# sch.net
KiCad netlist of a schematic drawn in Altium Designer
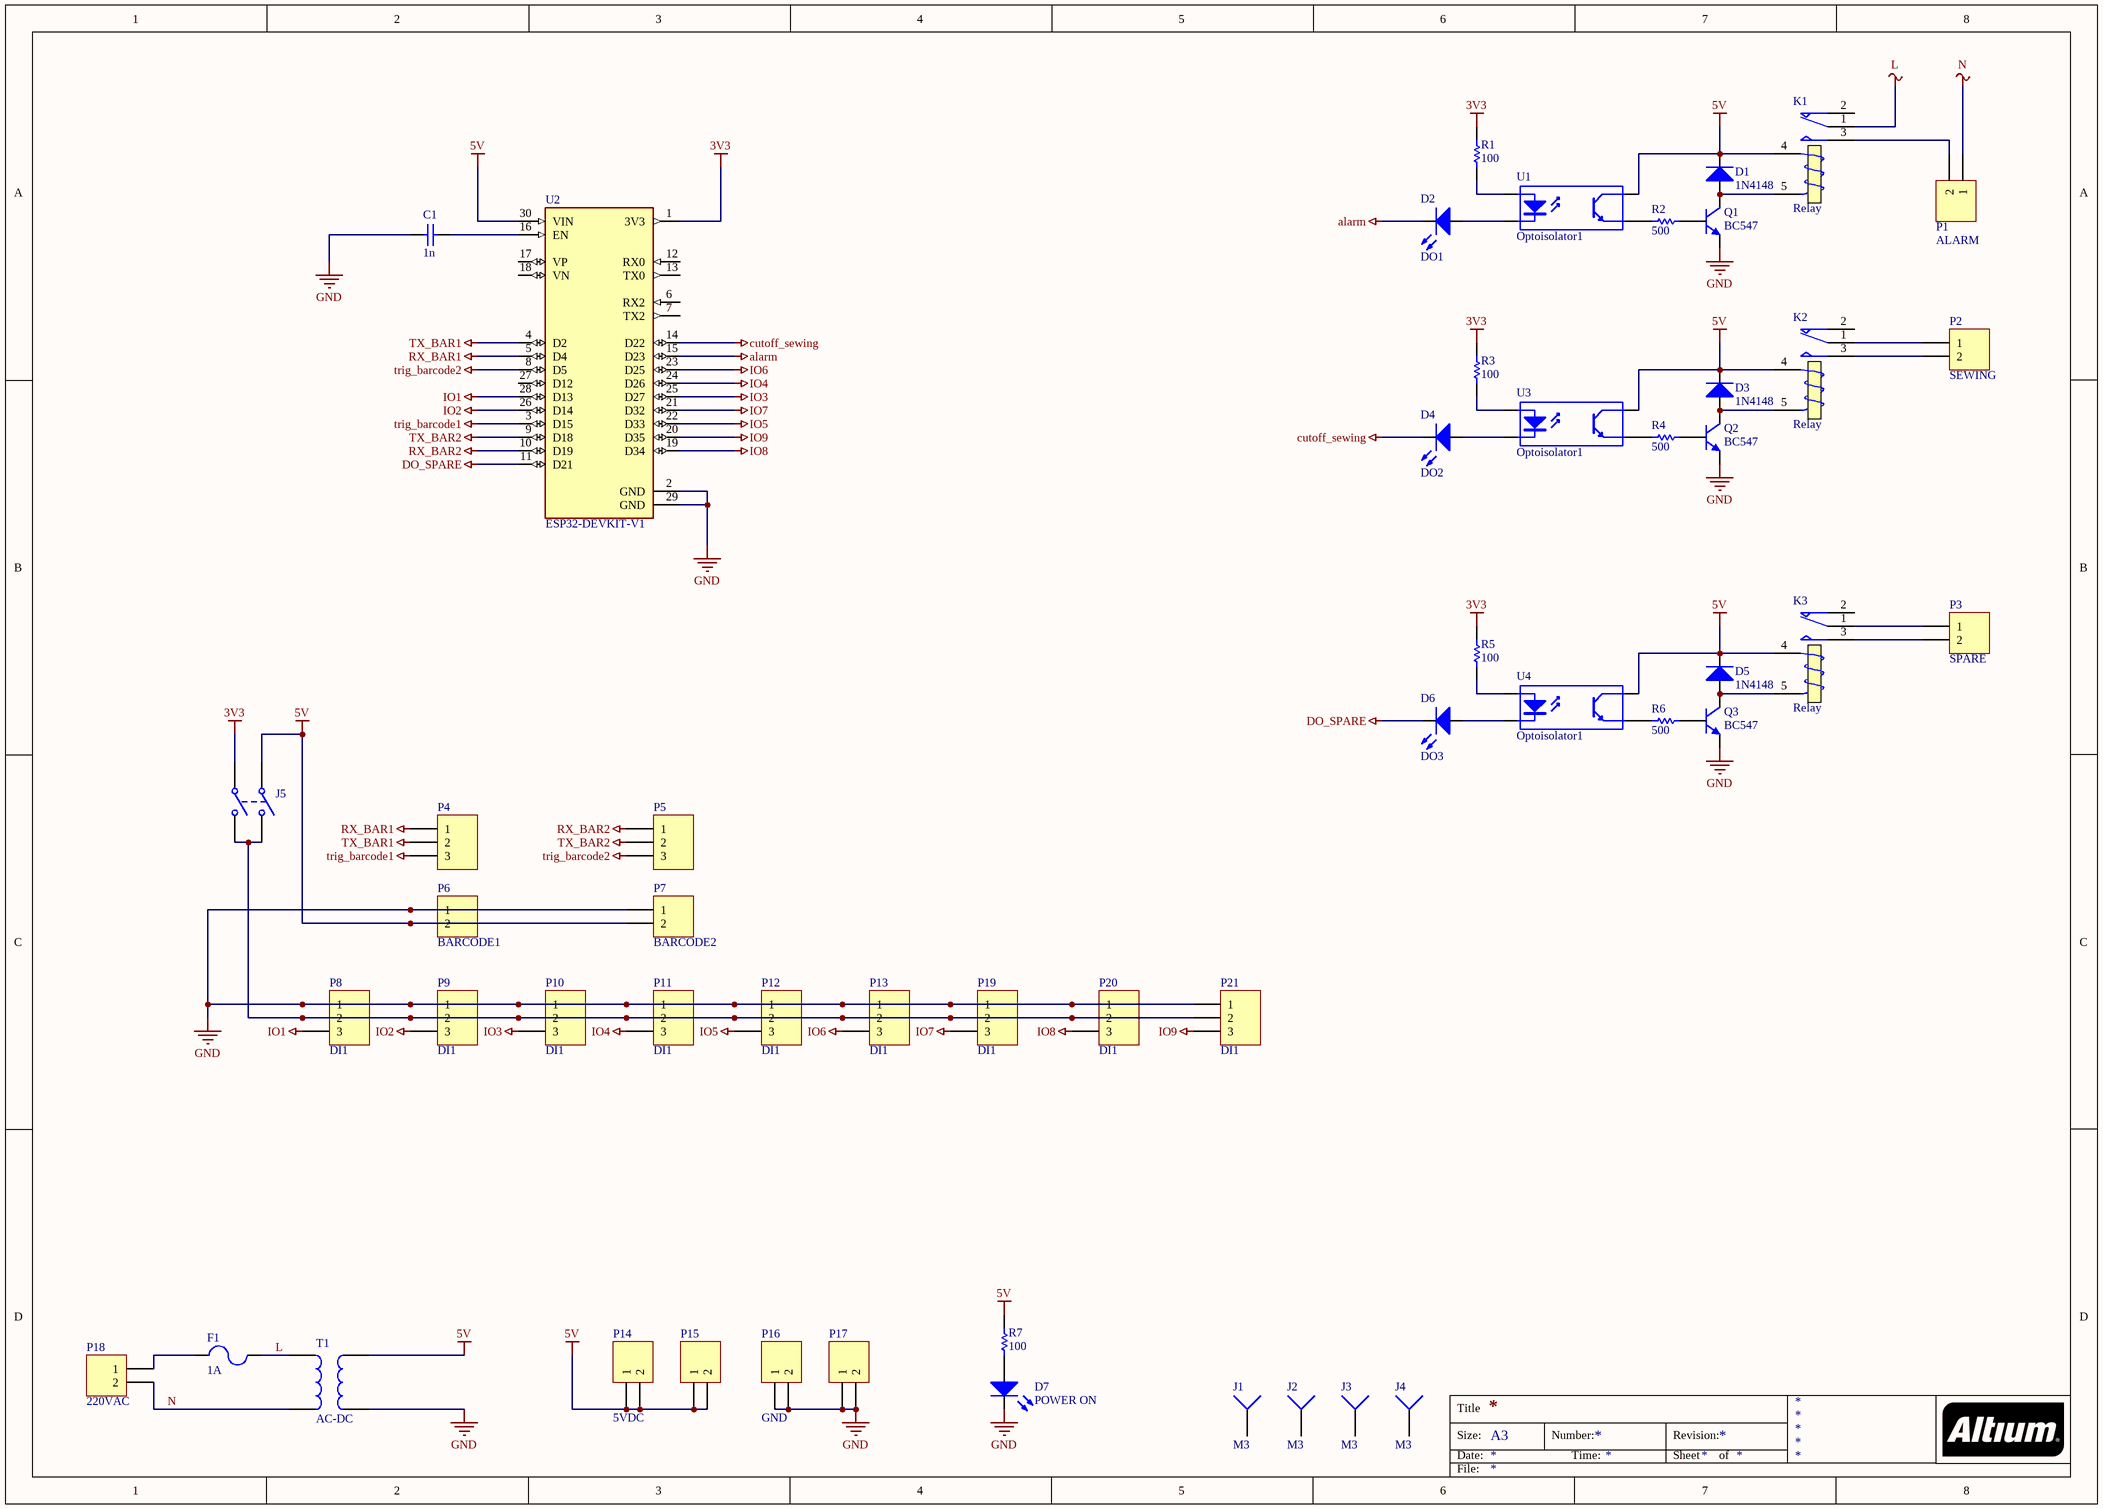
[diagram p0: sch.SchDoc]

(export (version "E")
  (design (tool "Eeschema 10.0.6"))
  (components
    (comp (ref "C1")
      (value "1n")
      (footprint "weerachai:CR2012-0805")
      (description "Capacitor")
      (fields (field (name "PUBLISHER") "Altium Limited"))
      (libsource (lib "Miscellaneous Devices") (part "Cap"))
    )
    (comp (ref "D1")
      (value "1N4148")
      (footprint "weerachai:D4148")
      (description "Default Diode")
      (fields (field (name "PUBLISHER") "Altium Limited"))
      (libsource (lib "weerachai") (part "Diode"))
    )
    (comp (ref "D2")
      (value "DO1")
      (footprint "weerachai:LED")
      (description "Typical INFRARED GaAs LED")
      (fields (field (name "PUBLISHER") "Altium Limited"))
      (libsource (lib "weerachai") (part "LED0"))
    )
    (comp (ref "D3")
      (value "1N4148")
      (footprint "weerachai:D4148")
      (description "Default Diode")
      (fields (field (name "PUBLISHER") "Altium Limited"))
      (libsource (lib "weerachai") (part "Diode"))
    )
    (comp (ref "D4")
      (value "DO2")
      (footprint "weerachai:LED")
      (description "Typical INFRARED GaAs LED")
      (fields (field (name "PUBLISHER") "Altium Limited"))
      (libsource (lib "weerachai") (part "LED0"))
    )
    (comp (ref "D5")
      (value "1N4148")
      (footprint "weerachai:D4148")
      (description "Default Diode")
      (fields (field (name "PUBLISHER") "Altium Limited"))
      (libsource (lib "weerachai") (part "Diode"))
    )
    (comp (ref "D6")
      (value "DO3")
      (footprint "weerachai:LED")
      (description "Typical INFRARED GaAs LED")
      (fields (field (name "PUBLISHER") "Altium Limited"))
      (libsource (lib "weerachai") (part "LED0"))
    )
    (comp (ref "D7")
      (value "POWER ON")
      (footprint "weerachai:LED")
      (description "Typical INFRARED GaAs LED")
      (fields (field (name "PUBLISHER") "Altium Limited"))
      (libsource (lib "weerachai") (part "LED0"))
    )
    (comp (ref "F1")
      (value "1A")
      (footprint "weerachai:CAP5W")
      (description "Fuse")
      (fields (field (name "PUBLISHER") "Altium Limited"))
      (libsource (lib "weerachai") (part "Fuse 2"))
    )
    (comp (ref "J1")
      (value "M3")
      (footprint "weerachai:PAD")
      (description "Socket")
      (fields (field (name "PUBLISHER") "Altium Limited"))
      (libsource (lib "weerachai") (part "Socket"))
    )
    (comp (ref "J2")
      (value "M3")
      (footprint "weerachai:PAD")
      (description "Socket")
      (fields (field (name "PUBLISHER") "Altium Limited"))
      (libsource (lib "weerachai") (part "Socket"))
    )
    (comp (ref "J3")
      (value "M3")
      (footprint "weerachai:PAD")
      (description "Socket")
      (fields (field (name "PUBLISHER") "Altium Limited"))
      (libsource (lib "weerachai") (part "Socket"))
    )
    (comp (ref "J4")
      (value "M3")
      (footprint "weerachai:PAD")
      (description "Socket")
      (fields (field (name "PUBLISHER") "Altium Limited"))
      (libsource (lib "weerachai") (part "Socket"))
    )
    (comp (ref "J5")
      (value "~")
      (footprint "weerachai:sip2x2")
      (description "Double-Pole, Single-Throw Switch")
      (fields (field (name "PUBLISHER") "Altium Limited"))
      (libsource (lib "Miscellaneous Devices") (part "SW-DPST"))
    )
    (comp (ref "K1")
      (value "Relay")
      (footprint "weerachai:RELAY1CON_REV")
      (description "SPDT Relay")
      (fields (field (name "PUBLISHER") "Altium Limited"))
      (libsource (lib "weerachai") (part "Relay"))
    )
    (comp (ref "K2")
      (value "Relay")
      (footprint "weerachai:RELAY1CON_REV")
      (description "SPDT Relay")
      (fields (field (name "PUBLISHER") "Altium Limited"))
      (libsource (lib "weerachai") (part "Relay"))
    )
    (comp (ref "K3")
      (value "Relay")
      (footprint "weerachai:RELAY1CON_REV")
      (description "SPDT Relay")
      (fields (field (name "PUBLISHER") "Altium Limited"))
      (libsource (lib "weerachai") (part "Relay"))
    )
    (comp (ref "P1")
      (value "ALARM")
      (footprint "weerachai:KF142V-5.08-P2")
      (description "Header, 2-Pin")
      (fields (field (name "PUBLISHER") "Altium Limited"))
      (libsource (lib "") (part "Header 2_2"))
    )
    (comp (ref "P2")
      (value "SEWING")
      (footprint "weerachai:KF142V-5.08-P2")
      (description "Header, 2-Pin")
      (fields (field (name "PUBLISHER") "Altium Limited"))
      (libsource (lib "") (part "Header 2_1"))
    )
    (comp (ref "P3")
      (value "SPARE")
      (footprint "weerachai:KF142V-5.08-P2")
      (description "Header, 2-Pin")
      (fields (field (name "PUBLISHER") "Altium Limited"))
      (libsource (lib "") (part "Header 2_1"))
    )
    (comp (ref "P4")
      (value "~")
      (footprint "weerachai:CONNECT_W(3)")
      (description "Header, 3-Pin")
      (fields (field (name "PUBLISHER") "Altium Limited"))
      (libsource (lib "Miscellaneous Connectors") (part "Header 3"))
    )
    (comp (ref "P5")
      (value "~")
      (footprint "weerachai:CONNECT_W(3)")
      (description "Header, 3-Pin")
      (fields (field (name "PUBLISHER") "Altium Limited"))
      (libsource (lib "Miscellaneous Connectors") (part "Header 3"))
    )
    (comp (ref "P6")
      (value "BARCODE1")
      (footprint "weerachai:CONNECT_2.54_(2)")
      (description "Header, 2-Pin")
      (fields (field (name "PUBLISHER") "Altium Limited"))
      (libsource (lib "") (part "Header 2_1"))
    )
    (comp (ref "P7")
      (value "BARCODE2")
      (footprint "weerachai:CONNECT_2.54_(2)")
      (description "Header, 2-Pin")
      (fields (field (name "PUBLISHER") "Altium Limited"))
      (libsource (lib "") (part "Header 2_1"))
    )
    (comp (ref "P8")
      (value "DI1")
      (footprint "weerachai:CONNECT_W(3)")
      (description "Header, 3-Pin")
      (fields (field (name "PUBLISHER") "Altium Limited"))
      (libsource (lib "Miscellaneous Connectors") (part "Header 3"))
    )
    (comp (ref "P9")
      (value "DI1")
      (footprint "weerachai:CONNECT_W(3)")
      (description "Header, 3-Pin")
      (fields (field (name "PUBLISHER") "Altium Limited"))
      (libsource (lib "Miscellaneous Connectors") (part "Header 3"))
    )
    (comp (ref "P10")
      (value "DI1")
      (footprint "weerachai:CONNECT_W(3)")
      (description "Header, 3-Pin")
      (fields (field (name "PUBLISHER") "Altium Limited"))
      (libsource (lib "Miscellaneous Connectors") (part "Header 3"))
    )
    (comp (ref "P11")
      (value "DI1")
      (footprint "weerachai:CONNECT_W(3)")
      (description "Header, 3-Pin")
      (fields (field (name "PUBLISHER") "Altium Limited"))
      (libsource (lib "Miscellaneous Connectors") (part "Header 3"))
    )
    (comp (ref "P12")
      (value "DI1")
      (footprint "weerachai:CONNECT_W(3)")
      (description "Header, 3-Pin")
      (fields (field (name "PUBLISHER") "Altium Limited"))
      (libsource (lib "Miscellaneous Connectors") (part "Header 3"))
    )
    (comp (ref "P13")
      (value "DI1")
      (footprint "weerachai:CONNECT_W(3)")
      (description "Header, 3-Pin")
      (fields (field (name "PUBLISHER") "Altium Limited"))
      (libsource (lib "Miscellaneous Connectors") (part "Header 3"))
    )
    (comp (ref "P14")
      (value "5VDC")
      (footprint "weerachai:KF142V-5.08-P2")
      (description "Header, 2-Pin")
      (fields (field (name "PUBLISHER") "Altium Limited"))
      (libsource (lib "Miscellaneous Connectors") (part "Header 2"))
    )
    (comp (ref "P15")
      (value "~")
      (footprint "weerachai:KF142V-5.08-P2")
      (description "Header, 2-Pin")
      (fields (field (name "PUBLISHER") "Altium Limited"))
      (libsource (lib "Miscellaneous Connectors") (part "Header 2"))
    )
    (comp (ref "P16")
      (value "GND")
      (footprint "weerachai:KF142V-5.08-P2")
      (description "Header, 2-Pin")
      (fields (field (name "PUBLISHER") "Altium Limited"))
      (libsource (lib "Miscellaneous Connectors") (part "Header 2"))
    )
    (comp (ref "P17")
      (value "~")
      (footprint "weerachai:KF142V-5.08-P2")
      (description "Header, 2-Pin")
      (fields (field (name "PUBLISHER") "Altium Limited"))
      (libsource (lib "Miscellaneous Connectors") (part "Header 2"))
    )
    (comp (ref "P18")
      (value "220VAC")
      (footprint "weerachai:KF142V-5.08-P2")
      (description "Header, 2-Pin")
      (fields (field (name "PUBLISHER") "Altium Limited"))
      (libsource (lib "") (part "Header 2_2"))
    )
    (comp (ref "P19")
      (value "DI1")
      (footprint "weerachai:CONNECT_W(3)")
      (description "Header, 3-Pin")
      (fields (field (name "PUBLISHER") "Altium Limited"))
      (libsource (lib "Miscellaneous Connectors") (part "Header 3"))
    )
    (comp (ref "P20")
      (value "DI1")
      (footprint "weerachai:CONNECT_W(3)")
      (description "Header, 3-Pin")
      (fields (field (name "PUBLISHER") "Altium Limited"))
      (libsource (lib "Miscellaneous Connectors") (part "Header 3"))
    )
    (comp (ref "P21")
      (value "DI1")
      (footprint "weerachai:CONNECT_W(3)")
      (description "Header, 3-Pin")
      (fields (field (name "PUBLISHER") "Altium Limited"))
      (libsource (lib "Miscellaneous Connectors") (part "Header 3"))
    )
    (comp (ref "Q1")
      (value "BC547")
      (footprint "weerachai:TO-92")
      (description "NPN General Purpose Amplifier")
      (fields (field (name "PUBLISHER") "Altium Limited"))
      (libsource (lib "weerachai") (part "2N3904"))
    )
    (comp (ref "Q2")
      (value "BC547")
      (footprint "weerachai:TO-92")
      (description "NPN General Purpose Amplifier")
      (fields (field (name "PUBLISHER") "Altium Limited"))
      (libsource (lib "weerachai") (part "2N3904"))
    )
    (comp (ref "Q3")
      (value "BC547")
      (footprint "weerachai:TO-92")
      (description "NPN General Purpose Amplifier")
      (fields (field (name "PUBLISHER") "Altium Limited"))
      (libsource (lib "weerachai") (part "2N3904"))
    )
    (comp (ref "R1")
      (value "100")
      (footprint "weerachai:R1/8")
      (description "Resistor")
      (fields (field (name "PUBLISHER") "Altium Limited"))
      (libsource (lib "weerachai") (part "Res1"))
    )
    (comp (ref "R2")
      (value "500")
      (footprint "weerachai:R1/8")
      (description "Resistor")
      (fields (field (name "PUBLISHER") "Altium Limited"))
      (libsource (lib "weerachai") (part "Res1"))
    )
    (comp (ref "R3")
      (value "100")
      (footprint "weerachai:R1/8")
      (description "Resistor")
      (fields (field (name "PUBLISHER") "Altium Limited"))
      (libsource (lib "weerachai") (part "Res1"))
    )
    (comp (ref "R4")
      (value "500")
      (footprint "weerachai:R1/8")
      (description "Resistor")
      (fields (field (name "PUBLISHER") "Altium Limited"))
      (libsource (lib "weerachai") (part "Res1"))
    )
    (comp (ref "R5")
      (value "100")
      (footprint "weerachai:R1/8")
      (description "Resistor")
      (fields (field (name "PUBLISHER") "Altium Limited"))
      (libsource (lib "weerachai") (part "Res1"))
    )
    (comp (ref "R6")
      (value "500")
      (footprint "weerachai:R1/8")
      (description "Resistor")
      (fields (field (name "PUBLISHER") "Altium Limited"))
      (libsource (lib "weerachai") (part "Res1"))
    )
    (comp (ref "R7")
      (value "100")
      (footprint "weerachai:R1/8")
      (description "Resistor")
      (fields (field (name "PUBLISHER") "Altium Limited"))
      (libsource (lib "weerachai") (part "Res1"))
    )
    (comp (ref "T1")
      (value "AC-DC")
      (footprint "weerachai:HLK-PM01")
      (description "Transformer")
      (fields (field (name "PUBLISHER") "Altium Limited"))
      (libsource (lib "weerachai") (part "Trans"))
    )
    (comp (ref "U1")
      (value "Optoisolator1")
      (footprint "weerachai:DIP-4 - TOP")
      (description "4-Pin Phototransistor Optocoupler")
      (fields (field (name "PUBLISHER") "Altium Limited"))
      (libsource (lib "weerachai") (part "Optoisolator1"))
    )
    (comp (ref "U2")
      (value "ESP32-DEVKIT-V1")
      (footprint "weerachai:ESP32_DEVKIT_V1")
      (libsource (lib "weerachai") (part "ESP32-DEVKIT-V1"))
    )
    (comp (ref "U3")
      (value "Optoisolator1")
      (footprint "weerachai:DIP-4 - TOP")
      (description "4-Pin Phototransistor Optocoupler")
      (fields (field (name "PUBLISHER") "Altium Limited"))
      (libsource (lib "weerachai") (part "Optoisolator1"))
    )
    (comp (ref "U4")
      (value "Optoisolator1")
      (footprint "weerachai:DIP-4 - TOP")
      (description "4-Pin Phototransistor Optocoupler")
      (fields (field (name "PUBLISHER") "Altium Limited"))
      (libsource (lib "weerachai") (part "Optoisolator1"))
    )
  )
  (nets
    (net (code "1") (name "3V3") (class "Default")
      (node (ref "J5") (pin "3") (pinfunction "COMMON2_3") (pintype "passive"))
      (node (ref "R1") (pin "2") (pinfunction "2_2") (pintype "passive"))
      (node (ref "R3") (pin "2") (pinfunction "2_2") (pintype "passive"))
      (node (ref "R5") (pin "2") (pinfunction "2_2") (pintype "passive"))
      (node (ref "U2") (pin "1") (pinfunction "3V3_1") (pintype "output"))
    )
    (net (code "2") (name "5V") (class "Default")
      (node (ref "D1") (pin "K") (pinfunction "K_K") (pintype "passive"))
      (node (ref "D3") (pin "K") (pinfunction "K_K") (pintype "passive"))
      (node (ref "D5") (pin "K") (pinfunction "K_K") (pintype "passive"))
      (node (ref "J5") (pin "1") (pinfunction "COMMON1_1") (pintype "passive"))
      (node (ref "K1") (pin "4") (pinfunction "T1_4") (pintype "passive"))
      (node (ref "K2") (pin "4") (pinfunction "T1_4") (pintype "passive"))
      (node (ref "K3") (pin "4") (pinfunction "T1_4") (pintype "passive"))
      (node (ref "P14") (pin "1") (pinfunction "1_1") (pintype "passive"))
      (node (ref "P14") (pin "2") (pinfunction "2_2") (pintype "passive"))
      (node (ref "P15") (pin "1") (pinfunction "1_1") (pintype "passive"))
      (node (ref "P15") (pin "2") (pinfunction "2_2") (pintype "passive"))
      (node (ref "P6") (pin "2") (pinfunction "2_2") (pintype "passive"))
      (node (ref "P7") (pin "2") (pinfunction "2_2") (pintype "passive"))
      (node (ref "R7") (pin "1") (pinfunction "1_1") (pintype "passive"))
      (node (ref "T1") (pin "4") (pinfunction "4_4") (pintype "passive"))
      (node (ref "U1") (pin "4") (pinfunction "C_4") (pintype "passive"))
      (node (ref "U2") (pin "30") (pinfunction "VIN_30") (pintype "input"))
      (node (ref "U3") (pin "4") (pinfunction "C_4") (pintype "passive"))
      (node (ref "U4") (pin "4") (pinfunction "C_4") (pintype "passive"))
    )
    (net (code "3") (name "DO_SPARE") (class "Default")
      (node (ref "D6") (pin "2") (pinfunction "K_2") (pintype "passive"))
      (node (ref "U2") (pin "11") (pinfunction "D21_11") (pintype "bidirectional"))
    )
    (net (code "4") (name "GND") (class "Default")
      (node (ref "C1") (pin "1") (pinfunction "1_1") (pintype "passive"))
      (node (ref "D7") (pin "2") (pinfunction "K_2") (pintype "passive"))
      (node (ref "P10") (pin "1") (pinfunction "1_1") (pintype "passive"))
      (node (ref "P11") (pin "1") (pinfunction "1_1") (pintype "passive"))
      (node (ref "P12") (pin "1") (pinfunction "1_1") (pintype "passive"))
      (node (ref "P13") (pin "1") (pinfunction "1_1") (pintype "passive"))
      (node (ref "P16") (pin "1") (pinfunction "1_1") (pintype "passive"))
      (node (ref "P16") (pin "2") (pinfunction "2_2") (pintype "passive"))
      (node (ref "P17") (pin "1") (pinfunction "1_1") (pintype "passive"))
      (node (ref "P17") (pin "2") (pinfunction "2_2") (pintype "passive"))
      (node (ref "P19") (pin "1") (pinfunction "1_1") (pintype "passive"))
      (node (ref "P20") (pin "1") (pinfunction "1_1") (pintype "passive"))
      (node (ref "P21") (pin "1") (pinfunction "1_1") (pintype "passive"))
      (node (ref "P6") (pin "1") (pinfunction "1_1") (pintype "passive"))
      (node (ref "P7") (pin "1") (pinfunction "1_1") (pintype "passive"))
      (node (ref "P8") (pin "1") (pinfunction "1_1") (pintype "passive"))
      (node (ref "P9") (pin "1") (pinfunction "1_1") (pintype "passive"))
      (node (ref "Q1") (pin "3") (pinfunction "E_3") (pintype "passive"))
      (node (ref "Q2") (pin "3") (pinfunction "E_3") (pintype "passive"))
      (node (ref "Q3") (pin "3") (pinfunction "E_3") (pintype "passive"))
      (node (ref "T1") (pin "3") (pinfunction "3_3") (pintype "passive"))
      (node (ref "U2") (pin "2") (pinfunction "GND_2") (pintype "power_in"))
      (node (ref "U2") (pin "29") (pinfunction "GND_29") (pintype "power_in"))
    )
    (net (code "5") (name "IO1") (class "Default")
      (node (ref "P8") (pin "3") (pinfunction "3_3") (pintype "passive"))
      (node (ref "U2") (pin "28") (pinfunction "D13_28") (pintype "bidirectional"))
    )
    (net (code "6") (name "IO2") (class "Default")
      (node (ref "P9") (pin "3") (pinfunction "3_3") (pintype "passive"))
      (node (ref "U2") (pin "26") (pinfunction "D14_26") (pintype "bidirectional"))
    )
    (net (code "7") (name "IO3") (class "Default")
      (node (ref "P10") (pin "3") (pinfunction "3_3") (pintype "passive"))
      (node (ref "U2") (pin "25") (pinfunction "D27_25") (pintype "bidirectional"))
    )
    (net (code "8") (name "IO4") (class "Default")
      (node (ref "P11") (pin "3") (pinfunction "3_3") (pintype "passive"))
      (node (ref "U2") (pin "24") (pinfunction "D26_24") (pintype "bidirectional"))
    )
    (net (code "9") (name "IO5") (class "Default")
      (node (ref "P12") (pin "3") (pinfunction "3_3") (pintype "passive"))
      (node (ref "U2") (pin "22") (pinfunction "D33_22") (pintype "bidirectional"))
    )
    (net (code "10") (name "IO6") (class "Default")
      (node (ref "P13") (pin "3") (pinfunction "3_3") (pintype "passive"))
      (node (ref "U2") (pin "23") (pinfunction "D25_23") (pintype "bidirectional"))
    )
    (net (code "11") (name "IO7") (class "Default")
      (node (ref "P19") (pin "3") (pinfunction "3_3") (pintype "passive"))
      (node (ref "U2") (pin "21") (pinfunction "D32_21") (pintype "bidirectional"))
    )
    (net (code "12") (name "IO8") (class "Default")
      (node (ref "P20") (pin "3") (pinfunction "3_3") (pintype "passive"))
      (node (ref "U2") (pin "19") (pinfunction "D34_19") (pintype "bidirectional"))
    )
    (net (code "13") (name "IO9") (class "Default")
      (node (ref "P21") (pin "3") (pinfunction "3_3") (pintype "passive"))
      (node (ref "U2") (pin "20") (pinfunction "D35_20") (pintype "bidirectional"))
    )
    (net (code "14") (name "L") (class "Default")
      (node (ref "F1") (pin "2") (pinfunction "2_2") (pintype "passive"))
      (node (ref "K1") (pin "1") (pinfunction "COM_1") (pintype "passive"))
      (node (ref "T1") (pin "2") (pinfunction "2_2") (pintype "passive"))
    )
    (net (code "15") (name "N") (class "Default")
      (node (ref "P1") (pin "1") (pinfunction "1_1") (pintype "passive"))
      (node (ref "P18") (pin "2") (pinfunction "2_2") (pintype "passive"))
      (node (ref "T1") (pin "1") (pinfunction "1_1") (pintype "passive"))
    )
    (net (code "16") (name "Net-(D2-A)") (class "Default")
      (node (ref "D2") (pin "1") (pinfunction "A_1") (pintype "passive"))
      (node (ref "U1") (pin "2") (pinfunction "K_2") (pintype "passive"))
    )
    (net (code "17") (name "Net-(D4-A)") (class "Default")
      (node (ref "D4") (pin "1") (pinfunction "A_1") (pintype "passive"))
      (node (ref "U3") (pin "2") (pinfunction "K_2") (pintype "passive"))
    )
    (net (code "18") (name "Net-(D6-A)") (class "Default")
      (node (ref "D6") (pin "1") (pinfunction "A_1") (pintype "passive"))
      (node (ref "U4") (pin "2") (pinfunction "K_2") (pintype "passive"))
    )
    (net (code "19") (name "Net-(D7-A)") (class "Default")
      (node (ref "D7") (pin "1") (pinfunction "A_1") (pintype "passive"))
      (node (ref "R7") (pin "2") (pinfunction "2_2") (pintype "passive"))
    )
    (net (code "20") (name "Net-(F1-Pad1)") (class "Default")
      (node (ref "F1") (pin "1") (pinfunction "1_1") (pintype "passive"))
      (node (ref "P18") (pin "1") (pinfunction "1_1") (pintype "passive"))
    )
    (net (code "21") (name "Net-(J5-NO1)") (class "Default")
      (node (ref "J5") (pin "2") (pinfunction "NO1_2") (pintype "passive"))
      (node (ref "J5") (pin "4") (pinfunction "NO2_4") (pintype "passive"))
      (node (ref "P10") (pin "2") (pinfunction "2_2") (pintype "passive"))
      (node (ref "P11") (pin "2") (pinfunction "2_2") (pintype "passive"))
      (node (ref "P12") (pin "2") (pinfunction "2_2") (pintype "passive"))
      (node (ref "P13") (pin "2") (pinfunction "2_2") (pintype "passive"))
      (node (ref "P19") (pin "2") (pinfunction "2_2") (pintype "passive"))
      (node (ref "P20") (pin "2") (pinfunction "2_2") (pintype "passive"))
      (node (ref "P21") (pin "2") (pinfunction "2_2") (pintype "passive"))
      (node (ref "P8") (pin "2") (pinfunction "2_2") (pintype "passive"))
      (node (ref "P9") (pin "2") (pinfunction "2_2") (pintype "passive"))
    )
    (net (code "22") (name "Net-(K1-NO)") (class "Default")
      (node (ref "K1") (pin "3") (pinfunction "NO_3") (pintype "passive"))
      (node (ref "P1") (pin "2") (pinfunction "2_2") (pintype "passive"))
    )
    (net (code "23") (name "Net-(K1-T2)") (class "Default")
      (node (ref "D1") (pin "A") (pinfunction "A_A") (pintype "passive"))
      (node (ref "K1") (pin "5") (pinfunction "T2_5") (pintype "passive"))
      (node (ref "Q1") (pin "1") (pinfunction "C_1") (pintype "passive"))
    )
    (net (code "24") (name "Net-(K2-COM)") (class "Default")
      (node (ref "K2") (pin "1") (pinfunction "COM_1") (pintype "passive"))
      (node (ref "P2") (pin "1") (pinfunction "1_1") (pintype "passive"))
    )
    (net (code "25") (name "Net-(K2-NO)") (class "Default")
      (node (ref "K2") (pin "3") (pinfunction "NO_3") (pintype "passive"))
      (node (ref "P2") (pin "2") (pinfunction "2_2") (pintype "passive"))
    )
    (net (code "26") (name "Net-(K2-T2)") (class "Default")
      (node (ref "D3") (pin "A") (pinfunction "A_A") (pintype "passive"))
      (node (ref "K2") (pin "5") (pinfunction "T2_5") (pintype "passive"))
      (node (ref "Q2") (pin "1") (pinfunction "C_1") (pintype "passive"))
    )
    (net (code "27") (name "Net-(K3-COM)") (class "Default")
      (node (ref "K3") (pin "1") (pinfunction "COM_1") (pintype "passive"))
      (node (ref "P3") (pin "1") (pinfunction "1_1") (pintype "passive"))
    )
    (net (code "28") (name "Net-(K3-NO)") (class "Default")
      (node (ref "K3") (pin "3") (pinfunction "NO_3") (pintype "passive"))
      (node (ref "P3") (pin "2") (pinfunction "2_2") (pintype "passive"))
    )
    (net (code "29") (name "Net-(K3-T2)") (class "Default")
      (node (ref "D5") (pin "A") (pinfunction "A_A") (pintype "passive"))
      (node (ref "K3") (pin "5") (pinfunction "T2_5") (pintype "passive"))
      (node (ref "Q3") (pin "1") (pinfunction "C_1") (pintype "passive"))
    )
    (net (code "30") (name "Net-(Q1-B)") (class "Default")
      (node (ref "Q1") (pin "2") (pinfunction "B_2") (pintype "passive"))
      (node (ref "R2") (pin "1") (pinfunction "1_1") (pintype "passive"))
    )
    (net (code "31") (name "Net-(Q2-B)") (class "Default")
      (node (ref "Q2") (pin "2") (pinfunction "B_2") (pintype "passive"))
      (node (ref "R4") (pin "1") (pinfunction "1_1") (pintype "passive"))
    )
    (net (code "32") (name "Net-(Q3-B)") (class "Default")
      (node (ref "Q3") (pin "2") (pinfunction "B_2") (pintype "passive"))
      (node (ref "R6") (pin "1") (pinfunction "1_1") (pintype "passive"))
    )
    (net (code "33") (name "Net-(U1-A)") (class "Default")
      (node (ref "R1") (pin "1") (pinfunction "1_1") (pintype "passive"))
      (node (ref "U1") (pin "1") (pinfunction "A_1") (pintype "passive"))
    )
    (net (code "34") (name "Net-(U1-E)") (class "Default")
      (node (ref "R2") (pin "2") (pinfunction "2_2") (pintype "passive"))
      (node (ref "U1") (pin "3") (pinfunction "E_3") (pintype "passive"))
    )
    (net (code "35") (name "Net-(U2-EN)") (class "Default")
      (node (ref "C1") (pin "2") (pinfunction "2_2") (pintype "passive"))
      (node (ref "U2") (pin "16") (pinfunction "EN_16") (pintype "input"))
    )
    (net (code "36") (name "Net-(U3-A)") (class "Default")
      (node (ref "R3") (pin "1") (pinfunction "1_1") (pintype "passive"))
      (node (ref "U3") (pin "1") (pinfunction "A_1") (pintype "passive"))
    )
    (net (code "37") (name "Net-(U3-E)") (class "Default")
      (node (ref "R4") (pin "2") (pinfunction "2_2") (pintype "passive"))
      (node (ref "U3") (pin "3") (pinfunction "E_3") (pintype "passive"))
    )
    (net (code "38") (name "Net-(U4-A)") (class "Default")
      (node (ref "R5") (pin "1") (pinfunction "1_1") (pintype "passive"))
      (node (ref "U4") (pin "1") (pinfunction "A_1") (pintype "passive"))
    )
    (net (code "39") (name "Net-(U4-E)") (class "Default")
      (node (ref "R6") (pin "2") (pinfunction "2_2") (pintype "passive"))
      (node (ref "U4") (pin "3") (pinfunction "E_3") (pintype "passive"))
    )
    (net (code "40") (name "RX_BAR1") (class "Default")
      (node (ref "P4") (pin "1") (pinfunction "1_1") (pintype "passive"))
      (node (ref "U2") (pin "5") (pinfunction "D4_5") (pintype "bidirectional"))
    )
    (net (code "41") (name "RX_BAR2") (class "Default")
      (node (ref "P5") (pin "1") (pinfunction "1_1") (pintype "passive"))
      (node (ref "U2") (pin "10") (pinfunction "D19_10") (pintype "bidirectional"))
    )
    (net (code "42") (name "TX_BAR1") (class "Default")
      (node (ref "P4") (pin "2") (pinfunction "2_2") (pintype "passive"))
      (node (ref "U2") (pin "4") (pinfunction "D2_4") (pintype "bidirectional"))
    )
    (net (code "43") (name "TX_BAR2") (class "Default")
      (node (ref "P5") (pin "2") (pinfunction "2_2") (pintype "passive"))
      (node (ref "U2") (pin "9") (pinfunction "D18_9") (pintype "bidirectional"))
    )
    (net (code "44") (name "alarm") (class "Default")
      (node (ref "D2") (pin "2") (pinfunction "K_2") (pintype "passive"))
      (node (ref "U2") (pin "15") (pinfunction "D23_15") (pintype "bidirectional"))
    )
    (net (code "45") (name "cutoff_sewing") (class "Default")
      (node (ref "D4") (pin "2") (pinfunction "K_2") (pintype "passive"))
      (node (ref "U2") (pin "14") (pinfunction "D22_14") (pintype "bidirectional"))
    )
    (net (code "46") (name "trig_barcode1") (class "Default")
      (node (ref "P4") (pin "3") (pinfunction "3_3") (pintype "passive"))
      (node (ref "U2") (pin "3") (pinfunction "D15_3") (pintype "bidirectional"))
    )
    (net (code "47") (name "trig_barcode2") (class "Default")
      (node (ref "P5") (pin "3") (pinfunction "3_3") (pintype "passive"))
      (node (ref "U2") (pin "8") (pinfunction "D5_8") (pintype "bidirectional"))
    )
    (net (code "48") (name "unconnected-(J1-Pad1)") (class "Default")
      (node (ref "J1") (pin "1") (pinfunction "1_1") (pintype "passive"))
    )
    (net (code "49") (name "unconnected-(J2-Pad1)") (class "Default")
      (node (ref "J2") (pin "1") (pinfunction "1_1") (pintype "passive"))
    )
    (net (code "50") (name "unconnected-(J3-Pad1)") (class "Default")
      (node (ref "J3") (pin "1") (pinfunction "1_1") (pintype "passive"))
    )
    (net (code "51") (name "unconnected-(J4-Pad1)") (class "Default")
      (node (ref "J4") (pin "1") (pinfunction "1_1") (pintype "passive"))
    )
    (net (code "52") (name "unconnected-(K1-NC-Pad2)") (class "Default")
      (node (ref "K1") (pin "2") (pinfunction "NC_2") (pintype "passive"))
    )
    (net (code "53") (name "unconnected-(K2-NC-Pad2)") (class "Default")
      (node (ref "K2") (pin "2") (pinfunction "NC_2") (pintype "passive"))
    )
    (net (code "54") (name "unconnected-(K3-NC-Pad2)") (class "Default")
      (node (ref "K3") (pin "2") (pinfunction "NC_2") (pintype "passive"))
    )
    (net (code "55") (name "unconnected-(U2-D12-Pad27)") (class "Default")
      (node (ref "U2") (pin "27") (pinfunction "D12_27") (pintype "bidirectional"))
    )
    (net (code "56") (name "unconnected-(U2-RX0-Pad12)") (class "Default")
      (node (ref "U2") (pin "12") (pinfunction "RX0_12") (pintype "input"))
    )
    (net (code "57") (name "unconnected-(U2-RX2-Pad6)") (class "Default")
      (node (ref "U2") (pin "6") (pinfunction "RX2_6") (pintype "input"))
    )
    (net (code "58") (name "unconnected-(U2-TX0-Pad13)") (class "Default")
      (node (ref "U2") (pin "13") (pinfunction "TX0_13") (pintype "output"))
    )
    (net (code "59") (name "unconnected-(U2-TX2-Pad7)") (class "Default")
      (node (ref "U2") (pin "7") (pinfunction "TX2_7") (pintype "output"))
    )
    (net (code "60") (name "unconnected-(U2-VN-Pad18)") (class "Default")
      (node (ref "U2") (pin "18") (pinfunction "VN_18") (pintype "bidirectional"))
    )
    (net (code "61") (name "unconnected-(U2-VP-Pad17)") (class "Default")
      (node (ref "U2") (pin "17") (pinfunction "VP_17") (pintype "bidirectional"))
    )
  )
)
